# Sound_Study_Modular_EQ_PCB.net
KiCad netlist of a schematic drawn in EAGLE
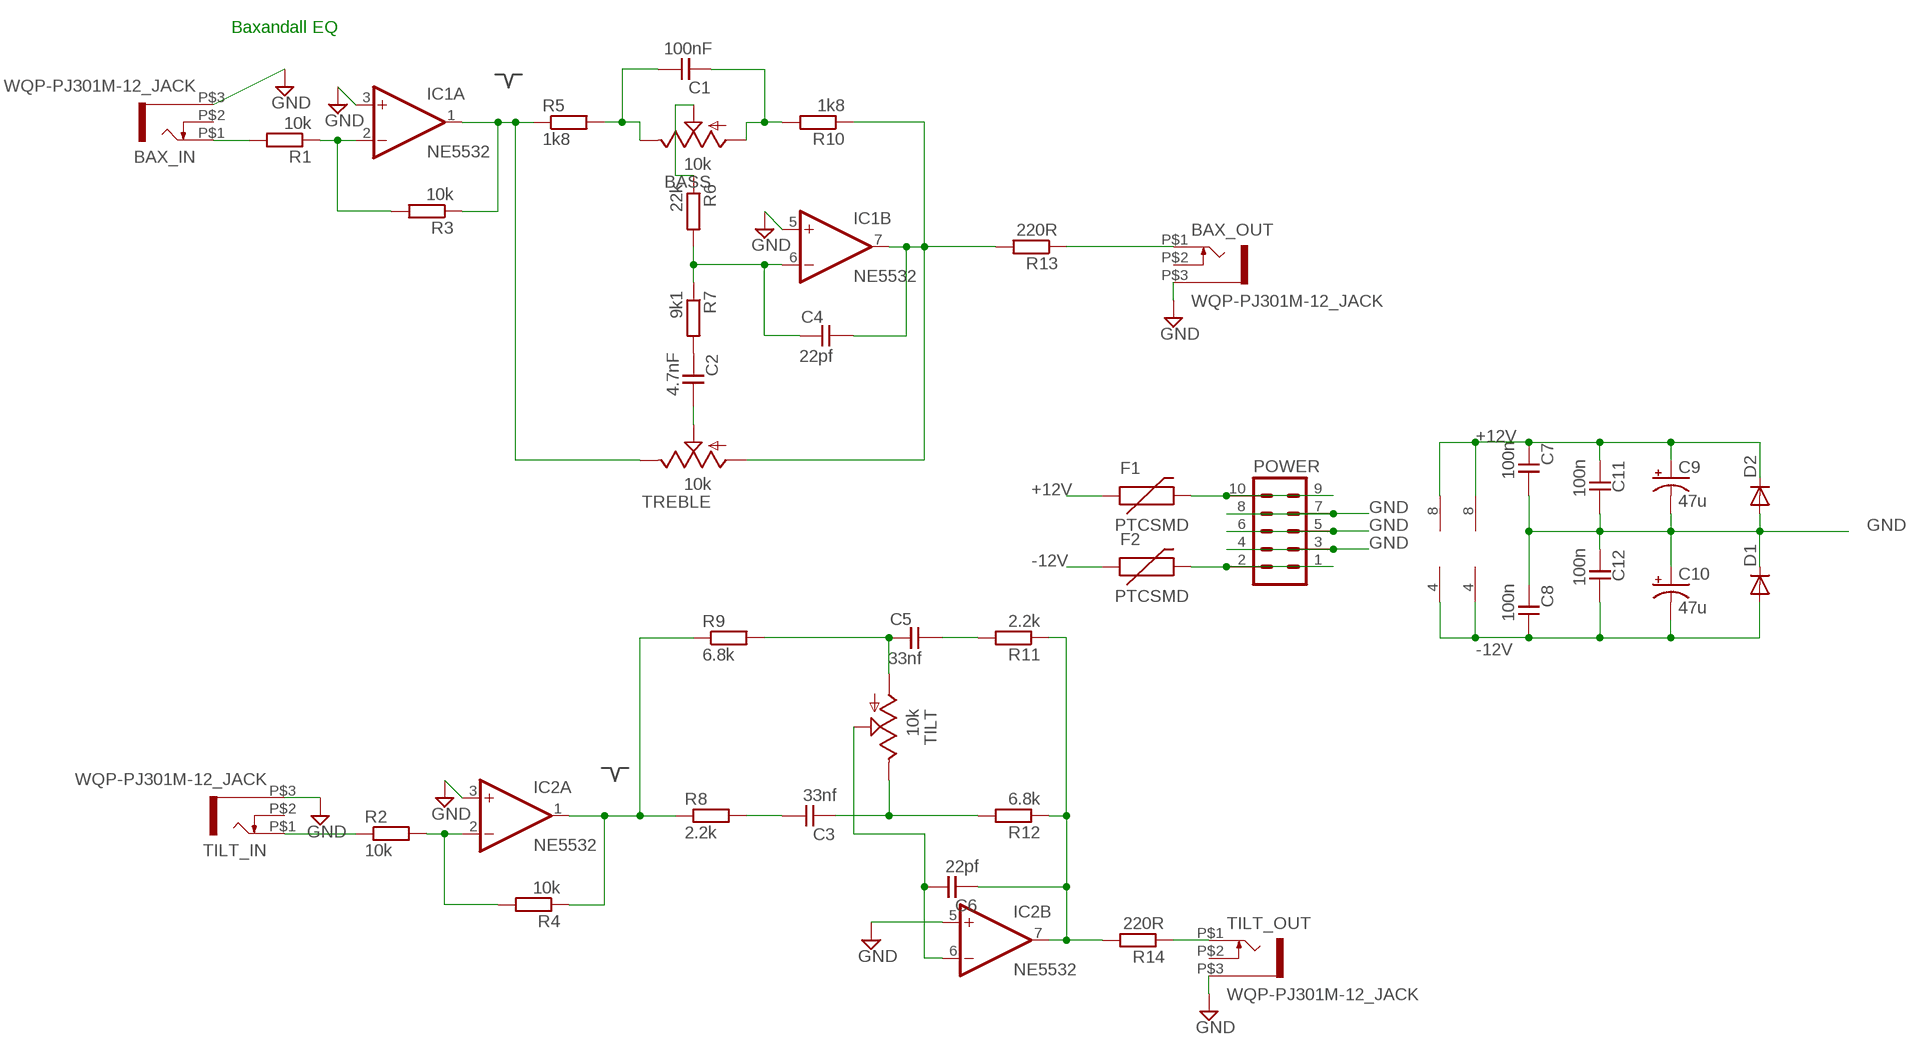
[diagram p0: schematic, sheet 1]

(export (version "E")
  (design (tool "Eeschema 10.0.6"))
  (components
    (comp (ref "BASS")
      (value "10k")
      (footprint "eagle-import:EVUF")
      (libsource (lib "eagle-import") (part "ALPHA-9MMAF2"))
    )
    (comp (ref "BAX_IN")
      (value "WQP-PJ301M-12_JACK")
      (footprint "eagle-import:WQP-PJ301M-12_JACK")
      (libsource (lib "eagle-import") (part "WQP-PJ301M-12_JACK"))
    )
    (comp (ref "BAX_OUT")
      (value "WQP-PJ301M-12_JACK")
      (footprint "eagle-import:WQP-PJ301M-12_JACK")
      (libsource (lib "eagle-import") (part "WQP-PJ301M-12_JACK"))
    )
    (comp (ref "C1")
      (value "100nF")
      (footprint "eagle-import:R0805")
      (libsource (lib "eagle-import") (part "C-EU0805_CAP"))
    )
    (comp (ref "C2")
      (value "4.7nF")
      (footprint "eagle-import:R0805")
      (libsource (lib "eagle-import") (part "C-EU0805_CAP"))
    )
    (comp (ref "C3")
      (value "33nf")
      (footprint "eagle-import:R0805")
      (libsource (lib "eagle-import") (part "C-EU0805_CAP"))
    )
    (comp (ref "C4")
      (value "22pf")
      (footprint "eagle-import:R0805")
      (libsource (lib "eagle-import") (part "C-EU0805_CAP"))
    )
    (comp (ref "C5")
      (value "33nf")
      (footprint "eagle-import:R0805")
      (libsource (lib "eagle-import") (part "C-EU0805_CAP"))
    )
    (comp (ref "C6")
      (value "22pf")
      (footprint "eagle-import:R0805")
      (libsource (lib "eagle-import") (part "C-EU0805_CAP"))
    )
    (comp (ref "C7")
      (value "100n")
      (footprint "eagle-import:R0805")
      (libsource (lib "eagle-import") (part "C-EU0805_CAP"))
    )
    (comp (ref "C8")
      (value "100n")
      (footprint "eagle-import:R0805")
      (libsource (lib "eagle-import") (part "C-EU0805_CAP"))
    )
    (comp (ref "C9")
      (value "47u")
      (footprint "eagle-import:PANASONIC_D")
      (libsource (lib "eagle-import") (part "CPOL-USD"))
    )
    (comp (ref "C10")
      (value "47u")
      (footprint "eagle-import:PANASONIC_D")
      (libsource (lib "eagle-import") (part "CPOL-USD"))
    )
    (comp (ref "C11")
      (value "100n")
      (footprint "eagle-import:R0805")
      (libsource (lib "eagle-import") (part "C-EU0805_CAP"))
    )
    (comp (ref "C12")
      (value "100n")
      (footprint "eagle-import:R0805")
      (libsource (lib "eagle-import") (part "C-EU0805_CAP"))
    )
    (comp (ref "D1")
      (value "DIODE-SOD123")
      (footprint "eagle-import:SOD123")
      (libsource (lib "eagle-import") (part "DIODE-SOD123"))
    )
    (comp (ref "D2")
      (value "DIODE-SOD123")
      (footprint "eagle-import:SOD123")
      (libsource (lib "eagle-import") (part "DIODE-SOD123"))
    )
    (comp (ref "F1")
      (value "PTCSMD")
      (footprint "eagle-import:PTC-1206")
      (libsource (lib "eagle-import") (part "PTCSMD"))
    )
    (comp (ref "F2")
      (value "PTCSMD")
      (footprint "eagle-import:PTC-1206")
      (libsource (lib "eagle-import") (part "PTCSMD"))
    )
    (comp (ref "IC1")
      (value "NE5532")
      (footprint "eagle-import:SO08")
      (libsource (lib "eagle-import") (part "TL072D"))
    )
    (comp (ref "IC2")
      (value "NE5532")
      (footprint "eagle-import:SO08")
      (libsource (lib "eagle-import") (part "TL072D"))
    )
    (comp (ref "POWER")
      (value "10_PIN_HEADER")
      (footprint "eagle-import:MA05-2")
      (libsource (lib "eagle-import") (part "10_PIN_HEADER"))
    )
    (comp (ref "R1")
      (value "10k")
      (footprint "eagle-import:R0805")
      (libsource (lib "eagle-import") (part "R-EU_R0805"))
    )
    (comp (ref "R2")
      (value "10k")
      (footprint "eagle-import:R0805")
      (libsource (lib "eagle-import") (part "R-EU_R0805"))
    )
    (comp (ref "R3")
      (value "10k")
      (footprint "eagle-import:R0805")
      (libsource (lib "eagle-import") (part "R-EU_R0805"))
    )
    (comp (ref "R4")
      (value "10k")
      (footprint "eagle-import:R0805")
      (libsource (lib "eagle-import") (part "R-EU_R0805"))
    )
    (comp (ref "R5")
      (value "1k8")
      (footprint "eagle-import:R0805")
      (libsource (lib "eagle-import") (part "R-EU_R0805"))
    )
    (comp (ref "R6")
      (value "22k")
      (footprint "eagle-import:R0805")
      (libsource (lib "eagle-import") (part "R-EU_R0805"))
    )
    (comp (ref "R7")
      (value "9k1")
      (footprint "eagle-import:R0805")
      (libsource (lib "eagle-import") (part "R-EU_R0805"))
    )
    (comp (ref "R8")
      (value "2.2k")
      (footprint "eagle-import:R0805")
      (libsource (lib "eagle-import") (part "R-EU_R0805"))
    )
    (comp (ref "R9")
      (value "6.8k")
      (footprint "eagle-import:R0805")
      (libsource (lib "eagle-import") (part "R-EU_R0805"))
    )
    (comp (ref "R10")
      (value "1k8")
      (footprint "eagle-import:R0805")
      (libsource (lib "eagle-import") (part "R-EU_R0805"))
    )
    (comp (ref "R11")
      (value "2.2k")
      (footprint "eagle-import:R0805")
      (libsource (lib "eagle-import") (part "R-EU_R0805"))
    )
    (comp (ref "R12")
      (value "6.8k")
      (footprint "eagle-import:R0805")
      (libsource (lib "eagle-import") (part "R-EU_R0805"))
    )
    (comp (ref "R13")
      (value "220R")
      (footprint "eagle-import:R0805")
      (libsource (lib "eagle-import") (part "R-EU_R0805"))
    )
    (comp (ref "R14")
      (value "220R")
      (footprint "eagle-import:R0805")
      (libsource (lib "eagle-import") (part "R-EU_R0805"))
    )
    (comp (ref "TILT")
      (value "10k")
      (footprint "eagle-import:EVUF")
      (libsource (lib "eagle-import") (part "ALPHA-9MMAF2"))
    )
    (comp (ref "TILT_IN")
      (value "WQP-PJ301M-12_JACK")
      (footprint "eagle-import:WQP-PJ301M-12_JACK")
      (libsource (lib "eagle-import") (part "WQP-PJ301M-12_JACK"))
    )
    (comp (ref "TILT_OUT")
      (value "WQP-PJ301M-12_JACK")
      (footprint "eagle-import:WQP-PJ301M-12_JACK")
      (libsource (lib "eagle-import") (part "WQP-PJ301M-12_JACK"))
    )
    (comp (ref "TREBLE")
      (value "10k")
      (footprint "eagle-import:EVUF")
      (libsource (lib "eagle-import") (part "ALPHA-9MMAF2"))
    )
  )
  (nets
    (net (code "1") (name "/+12V") (class "Default")
      (node (ref "C11") (pin "2") (pinfunction "2_2") (pintype "passive"))
      (node (ref "C7") (pin "2") (pinfunction "2_2") (pintype "passive"))
      (node (ref "C9") (pin "+") (pinfunction "+_+") (pintype "passive"))
      (node (ref "D2") (pin "C") (pinfunction "C_C") (pintype "passive"))
      (node (ref "F1") (pin "1") (pinfunction "1_1") (pintype "bidirectional"))
      (node (ref "IC1") (pin "8") (pinfunction "V+_8") (pintype "power_in"))
      (node (ref "IC2") (pin "8") (pinfunction "V+_8") (pintype "power_in"))
    )
    (net (code "2") (name "/-12V") (class "Default")
      (node (ref "C10") (pin "-") (pinfunction "-_-") (pintype "passive"))
      (node (ref "C12") (pin "1") (pinfunction "1_1") (pintype "passive"))
      (node (ref "C8") (pin "1") (pinfunction "1_1") (pintype "passive"))
      (node (ref "D1") (pin "A") (pinfunction "A_A") (pintype "passive"))
      (node (ref "F2") (pin "1") (pinfunction "1_1") (pintype "bidirectional"))
      (node (ref "IC1") (pin "4") (pinfunction "V-_4") (pintype "power_in"))
      (node (ref "IC2") (pin "4") (pinfunction "V-_4") (pintype "power_in"))
    )
    (net (code "3") (name "GND") (class "Default")
      (node (ref "BAX_IN") (pin "P$3") (pinfunction "1_P$3") (pintype "passive"))
      (node (ref "BAX_OUT") (pin "P$3") (pinfunction "1_P$3") (pintype "passive"))
      (node (ref "C10") (pin "+") (pinfunction "+_+") (pintype "passive"))
      (node (ref "C11") (pin "1") (pinfunction "1_1") (pintype "passive"))
      (node (ref "C12") (pin "2") (pinfunction "2_2") (pintype "passive"))
      (node (ref "C7") (pin "1") (pinfunction "1_1") (pintype "passive"))
      (node (ref "C8") (pin "2") (pinfunction "2_2") (pintype "passive"))
      (node (ref "C9") (pin "-") (pinfunction "-_-") (pintype "passive"))
      (node (ref "D1") (pin "C") (pinfunction "C_C") (pintype "passive"))
      (node (ref "D2") (pin "A") (pinfunction "A_A") (pintype "passive"))
      (node (ref "IC1") (pin "3") (pinfunction "+IN_3") (pintype "input"))
      (node (ref "IC1") (pin "5") (pinfunction "+IN_5") (pintype "input"))
      (node (ref "IC2") (pin "3") (pinfunction "+IN_3") (pintype "input"))
      (node (ref "IC2") (pin "5") (pinfunction "+IN_5") (pintype "input"))
      (node (ref "POWER") (pin "3") (pinfunction "3_3") (pintype "passive"))
      (node (ref "POWER") (pin "4") (pinfunction "4_4") (pintype "passive"))
      (node (ref "POWER") (pin "5") (pinfunction "5_5") (pintype "passive"))
      (node (ref "POWER") (pin "6") (pinfunction "6_6") (pintype "passive"))
      (node (ref "POWER") (pin "7") (pinfunction "7_7") (pintype "passive"))
      (node (ref "POWER") (pin "8") (pinfunction "8_8") (pintype "passive"))
      (node (ref "TILT_IN") (pin "P$3") (pinfunction "1_P$3") (pintype "passive"))
      (node (ref "TILT_OUT") (pin "P$3") (pinfunction "1_P$3") (pintype "passive"))
    )
    (net (code "4") (name "Net-(BASS-A)") (class "Default")
      (node (ref "BASS") (pin "1") (pinfunction "A_1") (pintype "passive"))
      (node (ref "C1") (pin "2") (pinfunction "2_2") (pintype "passive"))
      (node (ref "R10") (pin "2") (pinfunction "2_2") (pintype "passive"))
    )
    (net (code "5") (name "Net-(BASS-E)") (class "Default")
      (node (ref "BASS") (pin "3") (pinfunction "E_3") (pintype "passive"))
      (node (ref "C1") (pin "1") (pinfunction "1_1") (pintype "passive"))
      (node (ref "R5") (pin "2") (pinfunction "2_2") (pintype "passive"))
    )
    (net (code "6") (name "Net-(BASS-S)") (class "Default")
      (node (ref "BASS") (pin "2") (pinfunction "S_2") (pintype "passive"))
      (node (ref "R6") (pin "1") (pinfunction "1_1") (pintype "passive"))
    )
    (net (code "7") (name "Net-(BAX_IN-2)") (class "Default")
      (node (ref "BAX_IN") (pin "P$1") (pinfunction "2_P$1") (pintype "passive"))
      (node (ref "R1") (pin "2") (pinfunction "2_2") (pintype "passive"))
    )
    (net (code "8") (name "Net-(BAX_OUT-2)") (class "Default")
      (node (ref "BAX_OUT") (pin "P$1") (pinfunction "2_P$1") (pintype "passive"))
      (node (ref "R13") (pin "1") (pinfunction "1_1") (pintype "passive"))
    )
    (net (code "9") (name "Net-(C2-Pad2)") (class "Default")
      (node (ref "C2") (pin "2") (pinfunction "2_2") (pintype "passive"))
      (node (ref "R7") (pin "2") (pinfunction "2_2") (pintype "passive"))
    )
    (net (code "10") (name "Net-(C3-Pad1)") (class "Default")
      (node (ref "C3") (pin "1") (pinfunction "1_1") (pintype "passive"))
      (node (ref "R8") (pin "2") (pinfunction "2_2") (pintype "passive"))
    )
    (net (code "11") (name "Net-(C5-Pad1)") (class "Default")
      (node (ref "C5") (pin "1") (pinfunction "1_1") (pintype "passive"))
      (node (ref "R11") (pin "2") (pinfunction "2_2") (pintype "passive"))
    )
    (net (code "12") (name "Net-(F1-Pad2)") (class "Default")
      (node (ref "F1") (pin "2") (pinfunction "2_2") (pintype "bidirectional"))
      (node (ref "POWER") (pin "10") (pinfunction "10_10") (pintype "passive"))
      (node (ref "POWER") (pin "9") (pinfunction "9_9") (pintype "passive"))
    )
    (net (code "13") (name "Net-(F2-Pad2)") (class "Default")
      (node (ref "F2") (pin "2") (pinfunction "2_2") (pintype "bidirectional"))
      (node (ref "POWER") (pin "1") (pinfunction "1_1") (pintype "passive"))
      (node (ref "POWER") (pin "2") (pinfunction "2_2") (pintype "passive"))
    )
    (net (code "14") (name "Net-(IC1A--IN)") (class "Default")
      (node (ref "IC1") (pin "2") (pinfunction "-IN_2") (pintype "input"))
      (node (ref "R1") (pin "1") (pinfunction "1_1") (pintype "passive"))
      (node (ref "R3") (pin "2") (pinfunction "2_2") (pintype "passive"))
    )
    (net (code "15") (name "Net-(IC1A-OUT)") (class "Default")
      (node (ref "IC1") (pin "1") (pinfunction "OUT_1") (pintype "output"))
      (node (ref "R3") (pin "1") (pinfunction "1_1") (pintype "passive"))
      (node (ref "R5") (pin "1") (pinfunction "1_1") (pintype "passive"))
      (node (ref "TREBLE") (pin "3") (pinfunction "E_3") (pintype "passive"))
    )
    (net (code "16") (name "Net-(IC1B--IN)") (class "Default")
      (node (ref "C4") (pin "2") (pinfunction "2_2") (pintype "passive"))
      (node (ref "IC1") (pin "6") (pinfunction "-IN_6") (pintype "input"))
      (node (ref "R6") (pin "2") (pinfunction "2_2") (pintype "passive"))
      (node (ref "R7") (pin "1") (pinfunction "1_1") (pintype "passive"))
    )
    (net (code "17") (name "Net-(IC1B-OUT)") (class "Default")
      (node (ref "C4") (pin "1") (pinfunction "1_1") (pintype "passive"))
      (node (ref "IC1") (pin "7") (pinfunction "OUT_7") (pintype "output"))
      (node (ref "R10") (pin "1") (pinfunction "1_1") (pintype "passive"))
      (node (ref "R13") (pin "2") (pinfunction "2_2") (pintype "passive"))
      (node (ref "TREBLE") (pin "1") (pinfunction "A_1") (pintype "passive"))
    )
    (net (code "18") (name "Net-(IC2A--IN)") (class "Default")
      (node (ref "IC2") (pin "2") (pinfunction "-IN_2") (pintype "input"))
      (node (ref "R2") (pin "2") (pinfunction "2_2") (pintype "passive"))
      (node (ref "R4") (pin "2") (pinfunction "2_2") (pintype "passive"))
    )
    (net (code "19") (name "Net-(IC2A-OUT)") (class "Default")
      (node (ref "IC2") (pin "1") (pinfunction "OUT_1") (pintype "output"))
      (node (ref "R4") (pin "1") (pinfunction "1_1") (pintype "passive"))
      (node (ref "R8") (pin "1") (pinfunction "1_1") (pintype "passive"))
      (node (ref "R9") (pin "1") (pinfunction "1_1") (pintype "passive"))
    )
    (net (code "20") (name "Net-(IC2B--IN)") (class "Default")
      (node (ref "C6") (pin "1") (pinfunction "1_1") (pintype "passive"))
      (node (ref "IC2") (pin "6") (pinfunction "-IN_6") (pintype "input"))
      (node (ref "TILT") (pin "2") (pinfunction "S_2") (pintype "passive"))
    )
    (net (code "21") (name "Net-(IC2B-OUT)") (class "Default")
      (node (ref "C6") (pin "2") (pinfunction "2_2") (pintype "passive"))
      (node (ref "IC2") (pin "7") (pinfunction "OUT_7") (pintype "output"))
      (node (ref "R11") (pin "1") (pinfunction "1_1") (pintype "passive"))
      (node (ref "R12") (pin "1") (pinfunction "1_1") (pintype "passive"))
      (node (ref "R14") (pin "2") (pinfunction "2_2") (pintype "passive"))
    )
    (net (code "22") (name "Net-(TILT-A)") (class "Default")
      (node (ref "C5") (pin "2") (pinfunction "2_2") (pintype "passive"))
      (node (ref "R9") (pin "2") (pinfunction "2_2") (pintype "passive"))
      (node (ref "TILT") (pin "1") (pinfunction "A_1") (pintype "passive"))
    )
    (net (code "23") (name "Net-(TILT-E)") (class "Default")
      (node (ref "C3") (pin "2") (pinfunction "2_2") (pintype "passive"))
      (node (ref "R12") (pin "2") (pinfunction "2_2") (pintype "passive"))
      (node (ref "TILT") (pin "3") (pinfunction "E_3") (pintype "passive"))
    )
    (net (code "24") (name "Net-(TILT_IN-2)") (class "Default")
      (node (ref "R2") (pin "1") (pinfunction "1_1") (pintype "passive"))
      (node (ref "TILT_IN") (pin "P$1") (pinfunction "2_P$1") (pintype "passive"))
    )
    (net (code "25") (name "Net-(TILT_OUT-2)") (class "Default")
      (node (ref "R14") (pin "1") (pinfunction "1_1") (pintype "passive"))
      (node (ref "TILT_OUT") (pin "P$1") (pinfunction "2_P$1") (pintype "passive"))
    )
    (net (code "26") (name "Net-(TREBLE-S)") (class "Default")
      (node (ref "C2") (pin "1") (pinfunction "1_1") (pintype "passive"))
      (node (ref "TREBLE") (pin "2") (pinfunction "S_2") (pintype "passive"))
    )
    (net (code "27") (name "unconnected-(BAX_IN-3-PadP$2)") (class "Default")
      (node (ref "BAX_IN") (pin "P$2") (pinfunction "3_P$2") (pintype "passive"))
    )
    (net (code "28") (name "unconnected-(BAX_OUT-3-PadP$2)") (class "Default")
      (node (ref "BAX_OUT") (pin "P$2") (pinfunction "3_P$2") (pintype "passive"))
    )
    (net (code "29") (name "unconnected-(TILT_IN-3-PadP$2)") (class "Default")
      (node (ref "TILT_IN") (pin "P$2") (pinfunction "3_P$2") (pintype "passive"))
    )
    (net (code "30") (name "unconnected-(TILT_OUT-3-PadP$2)") (class "Default")
      (node (ref "TILT_OUT") (pin "P$2") (pinfunction "3_P$2") (pintype "passive"))
    )
  )
)
